# ble.net
KiCad netlist of a schematic drawn in Altium Designer
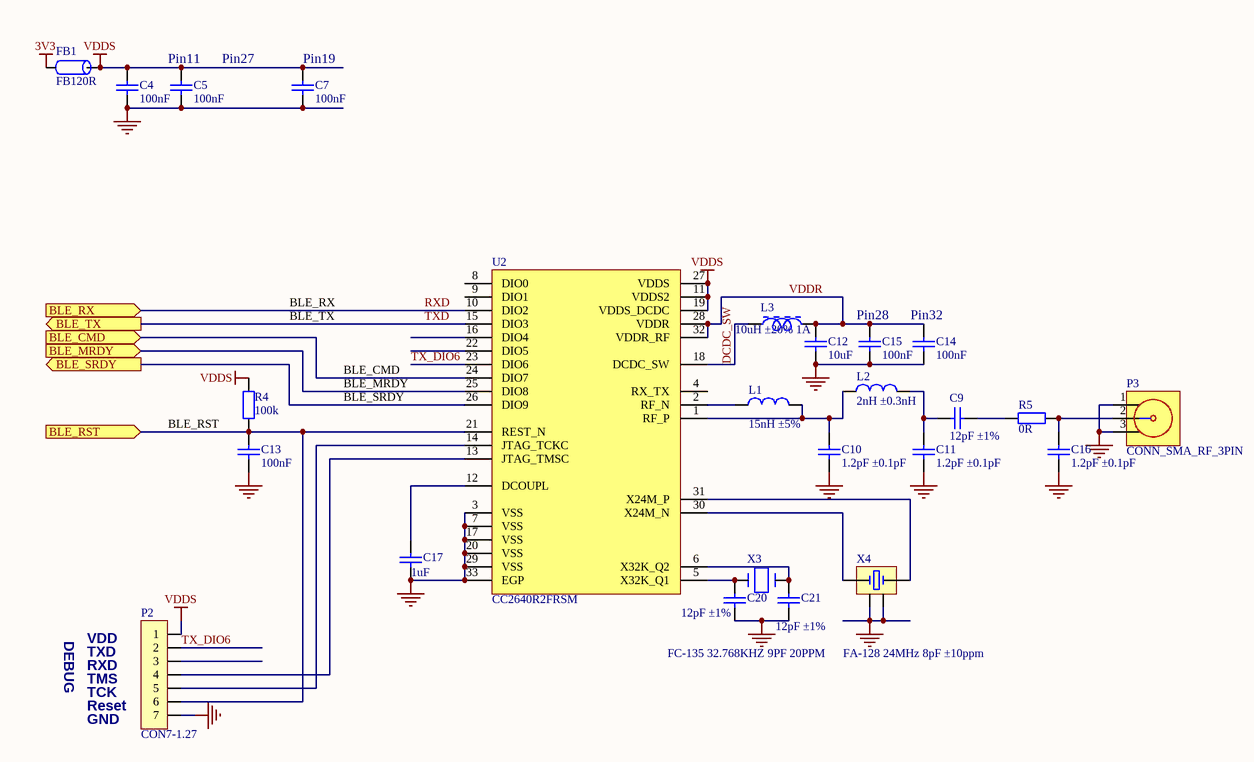
[diagram p0: ble.SchDoc]

(export (version "E")
  (design (tool "Eeschema 10.0.6"))
  (components
    (comp (ref "C4")
      (value "100nF")
      (footprint "0402_C")
      (description "表贴电容0402,±10%,16V,X7R")
      (fields (field (name "PART NUMBER") "RP02.04.000221") (field (name "PUBLISHER") "ChenYinaho"))
      (libsource (lib "tsl_Schlib") (part "Cap-0402_100n"))
    )
    (comp (ref "C5")
      (value "100nF")
      (footprint "0402_C")
      (description "表贴电容0402,±10%,16V,X7R")
      (fields (field (name "PART NUMBER") "RP02.04.000221") (field (name "PUBLISHER") "ChenYinaho"))
      (libsource (lib "tsl_Schlib") (part "Cap-0402_100n"))
    )
    (comp (ref "C7")
      (value "100nF")
      (footprint "0402_C")
      (description "表贴电容0402,±10%,16V,X7R")
      (fields (field (name "PART NUMBER") "RP02.04.000221") (field (name "PUBLISHER") "ChenYinaho"))
      (libsource (lib "tsl_Schlib") (part "Cap-0402_100n"))
    )
    (comp (ref "C9")
      (value "12pF ±1%")
      (footprint "0402_C")
      (description "表贴陶瓷电容,0402,±1%,50V,C0G")
      (fields
        (field (name "MANUFACTURER") "村田")
        (field (name "MANUFACTURER PART NUMBER") "GRM1555C1H120FA01D")
        (field (name "PUBLISHER") "ChenYinaho")
      )
      (libsource (lib "tsl_Schlib") (part "Cap-0402_12p_mu_1%"))
    )
    (comp (ref "C10")
      (value "1.2pF ±0.1pF")
      (footprint "0402_C")
      (description "表贴陶瓷电容,0402,±0.1pF,50V,C0G")
      (fields
        (field (name "MANUFACTURER") "村田")
        (field (name "MANUFACTURER PART NUMBER") "GRM1555C1H1R2BA01D")
        (field (name "PUBLISHER") "ChenYinaho")
      )
      (libsource (lib "tsl_Schlib") (part "Cap-0402_1.2p_mu"))
    )
    (comp (ref "C11")
      (value "1.2pF ±0.1pF")
      (footprint "0402_C")
      (description "表贴陶瓷电容,0402,±0.1pF,50V,C0G")
      (fields
        (field (name "MANUFACTURER") "村田")
        (field (name "MANUFACTURER PART NUMBER") "GRM1555C1H1R2BA01D")
        (field (name "PUBLISHER") "ChenYinaho")
      )
      (libsource (lib "tsl_Schlib") (part "Cap-0402_1.2p_mu"))
    )
    (comp (ref "C12")
      (value "10uF")
      (footprint "C0603")
      (description "表贴陶瓷电容,0603,±10%,10V")
      (fields
        (field (name "MANUFACTURER") "YAGO")
        (field (name "PART NUMBER") "RP02.04.000062")
        (field (name "PUBLISHER") "ChenYinaho")
      )
      (libsource (lib "tsl_Schlib") (part "Cap-SMT-0603_10u"))
    )
    (comp (ref "C13")
      (value "100nF")
      (footprint "0402_C")
      (description "表贴电容0402,±10%,16V,X7R")
      (fields (field (name "PART NUMBER") "RP02.04.000221") (field (name "PUBLISHER") "ChenYinaho"))
      (libsource (lib "tsl_Schlib") (part "Cap-0402_100n"))
    )
    (comp (ref "C14")
      (value "100nF")
      (footprint "0402_C")
      (description "表贴电容0402,±10%,16V,X7R")
      (fields (field (name "PART NUMBER") "RP02.04.000221") (field (name "PUBLISHER") "ChenYinaho"))
      (libsource (lib "tsl_Schlib") (part "Cap-0402_100n"))
    )
    (comp (ref "C15")
      (value "100nF")
      (footprint "0402_C")
      (description "表贴电容0402,±10%,16V,X7R")
      (fields (field (name "PART NUMBER") "RP02.04.000221") (field (name "PUBLISHER") "ChenYinaho"))
      (libsource (lib "tsl_Schlib") (part "Cap-0402_100n"))
    )
    (comp (ref "C16")
      (value "1.2pF ±0.1pF")
      (footprint "0402_C")
      (description "表贴陶瓷电容,0402,±0.1pF,50V,C0G")
      (fields
        (field (name "MANUFACTURER") "村田")
        (field (name "MANUFACTURER PART NUMBER") "GRM1555C1H1R2BA01D")
        (field (name "PUBLISHER") "ChenYinaho")
      )
      (libsource (lib "tsl_Schlib") (part "Cap-0402_1.2p_mu"))
    )
    (comp (ref "C17")
      (value "1uF")
      (footprint "0402_C")
      (description "表贴电容0402,±10%,6.3V")
      (fields (field (name "PART NUMBER") "RP02.04.000220") (field (name "PUBLISHER") "ChenYinaho"))
      (libsource (lib "tsl_Schlib") (part "Cap-0402_1u"))
    )
    (comp (ref "C20")
      (value "12pF ±1%")
      (footprint "0402_C")
      (description "表贴陶瓷电容,0402,±1%,50V,C0G")
      (fields
        (field (name "MANUFACTURER") "村田")
        (field (name "MANUFACTURER PART NUMBER") "GRM1555C1H120FA01D")
        (field (name "PUBLISHER") "ChenYinaho")
      )
      (libsource (lib "tsl_Schlib") (part "Cap-0402_12p_mu_1%"))
    )
    (comp (ref "C21")
      (value "12pF ±1%")
      (footprint "0402_C")
      (description "表贴陶瓷电容,0402,±1%,50V,C0G")
      (fields
        (field (name "MANUFACTURER") "村田")
        (field (name "MANUFACTURER PART NUMBER") "GRM1555C1H120FA01D")
        (field (name "PUBLISHER") "ChenYinaho")
      )
      (libsource (lib "tsl_Schlib") (part "Cap-0402_12p_mu_1%"))
    )
    (comp (ref "FB1")
      (value "FB120R")
      (footprint "L0603")
      (description "贴片磁珠")
      (fields
        (field (name "MANUFACTURER") "TDK")
        (field (name "PART NUMBER") "RP02.99.000093")
        (field (name "PUBLISHER") "ChenYinaho")
      )
      (libsource (lib "tsl_Schlib") (part "FB_0603_120R"))
    )
    (comp (ref "L1")
      (value "15nH ±5%")
      (footprint "LC-0402_L")
      (description "贴片电感 多层 0402 ±5% 450mA")
      (fields
        (field (name "MANUFACTURER") "村田")
        (field (name "MANUFACTURER PART NUMBER") "LQG15HS15NJ02D")
        (field (name "PUBLISHER") "ChenYinaho")
      )
      (libsource (lib "tsl_Schlib") (part "Inductor_0402_15nH"))
    )
    (comp (ref "L2")
      (value "2nH ±0.3nH")
      (footprint "LC-0402_L")
      (description "贴片电感 多层 0402 ±0.3nH 900mA")
      (fields
        (field (name "MANUFACTURER") "村田")
        (field (name "MANUFACTURER PART NUMBER") "LQG15HS2N0S02D")
        (field (name "PUBLISHER") "ChenYinaho")
      )
      (libsource (lib "tsl_Schlib") (part "Inductor_0402_2nH"))
    )
    (comp (ref "L3")
      (value "10uH ±20% 1A")
      (footprint "L0805")
      (description "贴片层叠电感")
      (fields
        (field (name "MANUFACTURER") "Sunlord")
        (field (name "MANUFACTURER PART NUMBER") "MPH201214S100MT")
        (field (name "PUBLISHER") "ChenYinaho")
      )
      (libsource (lib "tsl_Schlib") (part "Inductor_10uH_SL_0805"))
    )
    (comp (ref "P2")
      (value "CON7-1.27")
      (footprint "PH_7PIN_1.25_H-2")
      (description "直插插座")
      (fields (field (name "PART NUMBER") "RP02.07.000049") (field (name "PUBLISHER") "ChenYinaho"))
      (libsource (lib "tsl_Schlib") (part "CON7"))
    )
    (comp (ref "P3")
      (value "CONN_SMA_RF_3PIN")
      (footprint "PH_RF_2.5X2.5")
      (description "贴片天线座")
      (fields (field (name "PART NUMBER") "RP02.07.000078") (field (name "PUBLISHER") "ChenYinaho"))
      (libsource (lib "tsl_Schlib") (part "CONN_SMA_RF_3PIN"))
    )
    (comp (ref "R4")
      (value "100k")
      (footprint "0402_R")
      (description "表贴电阻,0402,±1%,1/16W")
      (fields (field (name "PART NUMBER") "NEW") (field (name "PUBLISHER") "ChenYinaho"))
      (libsource (lib "tsl_Schlib") (part "Res-0402_100k"))
    )
    (comp (ref "R5")
      (value "0R")
      (footprint "0402_R")
      (description "表贴电阻,0402,±1%,1/16W")
      (fields (field (name "PART NUMBER") "NEW") (field (name "PUBLISHER") "ChenYinaho"))
      (libsource (lib "tsl_Schlib") (part "Res-0402_0R"))
    )
    (comp (ref "U2")
      (value "CC2640R2FRSM")
      (footprint "VQFN-32_4x4x04P")
      (description "无线收发芯片")
      (fields
        (field (name "MANUFACTURER") "TI")
        (field (name "PART NUMBER") "NEW")
        (field (name "PUBLISHER") "ChenYinaho")
      )
      (libsource (lib "tsl_Schlib") (part "CC2640R2FRSM"))
    )
    (comp (ref "X3")
      (value "FC-135 32.768KHZ 9PF 20PPM")
      (footprint "FC-135")
      (description "贴片无源晶体3215")
      (fields
        (field (name "MANUFACTURER") "EPSON(爱普生)")
        (field (name "MANUFACTURER PART NUMBER") "FC-13532.768KHZ9PF20PPM")
        (field (name "PUBLISHER") "ChenYinaho")
      )
      (libsource (lib "tsl_Schlib") (part "XTAL-3215_2P_32k_9pF"))
    )
    (comp (ref "X4")
      (value "FA-128 24MHz 8pF ±10ppm")
      (footprint "FA-128")
      (description "贴片无源晶体2016")
      (fields
        (field (name "MANUFACTURER") "EPSON(爱普生)")
        (field (name "MANUFACTURER PART NUMBER") "Q22FA12800120")
        (field (name "PUBLISHER") "ChenYinaho")
      )
      (libsource (lib "tsl_Schlib") (part "XTAL-2016_4P_24M_8pF"))
    )
  )
  (nets
    (net (code "1") (name "/BLE_CMD") (class "Default")
      (node (ref "U2") (pin "24") (pinfunction "DIO7_24") (pintype "passive"))
    )
    (net (code "2") (name "/BLE_MRDY") (class "Default")
      (node (ref "U2") (pin "25") (pinfunction "DIO8_25") (pintype "passive"))
    )
    (net (code "3") (name "/BLE_RST") (class "Default")
      (node (ref "C13") (pin "1") (pinfunction "1_1") (pintype "passive"))
      (node (ref "P2") (pin "6") (pinfunction "6_6") (pintype "passive"))
      (node (ref "R4") (pin "1") (pinfunction "1_1") (pintype "passive"))
      (node (ref "U2") (pin "21") (pinfunction "REST_N_21") (pintype "passive"))
    )
    (net (code "4") (name "/BLE_RX") (class "Default")
      (node (ref "U2") (pin "10") (pinfunction "DIO2_10") (pintype "passive"))
    )
    (net (code "5") (name "/BLE_SRDY") (class "Default")
      (node (ref "U2") (pin "26") (pinfunction "DIO9_26") (pintype "passive"))
    )
    (net (code "6") (name "/BLE_TX") (class "Default")
      (node (ref "U2") (pin "15") (pinfunction "DIO3_15") (pintype "passive"))
    )
    (net (code "7") (name "/DCDC_SW") (class "Default")
      (node (ref "L3") (pin "2") (pintype "passive"))
      (node (ref "U2") (pin "18") (pinfunction "DCDC_SW_18") (pintype "passive"))
    )
    (net (code "8") (name "/TX_DIO6") (class "Default")
      (node (ref "P2") (pin "2") (pinfunction "2_2") (pintype "passive"))
      (node (ref "U2") (pin "23") (pinfunction "DIO6_23") (pintype "passive"))
    )
    (net (code "9") (name "/VDDR") (class "Default")
      (node (ref "C12") (pin "2") (pinfunction "2_2") (pintype "passive"))
      (node (ref "C14") (pin "1") (pinfunction "1_1") (pintype "passive"))
      (node (ref "C15") (pin "1") (pinfunction "1_1") (pintype "passive"))
      (node (ref "L3") (pin "1") (pintype "passive"))
      (node (ref "U2") (pin "28") (pinfunction "VDDR_28") (pintype "passive"))
      (node (ref "U2") (pin "32") (pinfunction "VDDR_RF_32") (pintype "passive"))
    )
    (net (code "10") (name "3V3") (class "Default") (node (ref "FB1") (pin "2") (pintype "passive")))
    (net (code "11") (name "GND") (class "Default")
      (node (ref "C10") (pin "1") (pinfunction "1_1") (pintype "passive"))
      (node (ref "C11") (pin "1") (pinfunction "1_1") (pintype "passive"))
      (node (ref "C12") (pin "1") (pinfunction "1_1") (pintype "passive"))
      (node (ref "C13") (pin "2") (pinfunction "2_2") (pintype "passive"))
      (node (ref "C14") (pin "2") (pinfunction "2_2") (pintype "passive"))
      (node (ref "C15") (pin "2") (pinfunction "2_2") (pintype "passive"))
      (node (ref "C16") (pin "1") (pinfunction "1_1") (pintype "passive"))
      (node (ref "C17") (pin "2") (pinfunction "2_2") (pintype "passive"))
      (node (ref "C20") (pin "1") (pinfunction "1_1") (pintype "passive"))
      (node (ref "C21") (pin "1") (pinfunction "1_1") (pintype "passive"))
      (node (ref "C4") (pin "2") (pinfunction "2_2") (pintype "passive"))
      (node (ref "C5") (pin "2") (pinfunction "2_2") (pintype "passive"))
      (node (ref "C7") (pin "2") (pinfunction "2_2") (pintype "passive"))
      (node (ref "P2") (pin "7") (pinfunction "7_7") (pintype "passive"))
      (node (ref "P3") (pin "1") (pintype "passive"))
      (node (ref "P3") (pin "3") (pintype "passive"))
      (node (ref "U2") (pin "17") (pinfunction "VSS_17") (pintype "passive"))
      (node (ref "U2") (pin "20") (pinfunction "VSS_20") (pintype "passive"))
      (node (ref "U2") (pin "29") (pinfunction "VSS_29") (pintype "passive"))
      (node (ref "U2") (pin "3") (pinfunction "VSS_3") (pintype "passive"))
      (node (ref "U2") (pin "33") (pinfunction "EGP_33") (pintype "passive"))
      (node (ref "U2") (pin "7") (pinfunction "VSS_7") (pintype "passive"))
      (node (ref "X4") (pin "2") (pintype "passive"))
      (node (ref "X4") (pin "4") (pintype "passive"))
    )
    (net (code "12") (name "Net-(C9-Pad1)") (class "Default")
      (node (ref "C9") (pin "1") (pinfunction "1_1") (pintype "passive"))
      (node (ref "R5") (pin "2") (pinfunction "2_2") (pintype "passive"))
    )
    (net (code "13") (name "Net-(C11-Pad2)") (class "Default")
      (node (ref "C11") (pin "2") (pinfunction "2_2") (pintype "passive"))
      (node (ref "C9") (pin "2") (pinfunction "2_2") (pintype "passive"))
      (node (ref "L2") (pin "1") (pintype "passive"))
    )
    (net (code "14") (name "Net-(C16-Pad2)") (class "Default")
      (node (ref "C16") (pin "2") (pinfunction "2_2") (pintype "passive"))
      (node (ref "P3") (pin "2") (pintype "passive"))
      (node (ref "R5") (pin "1") (pinfunction "1_1") (pintype "passive"))
    )
    (net (code "15") (name "Net-(U2-DCOUPL)") (class "Default")
      (node (ref "C17") (pin "1") (pinfunction "1_1") (pintype "passive"))
      (node (ref "U2") (pin "12") (pinfunction "DCOUPL_12") (pintype "passive"))
    )
    (net (code "16") (name "Net-(U2-JTAG_TCKC)") (class "Default")
      (node (ref "P2") (pin "5") (pinfunction "5_5") (pintype "passive"))
      (node (ref "U2") (pin "14") (pinfunction "JTAG_TCKC_14") (pintype "passive"))
    )
    (net (code "17") (name "Net-(U2-JTAG_TMSC)") (class "Default")
      (node (ref "P2") (pin "4") (pinfunction "4_4") (pintype "passive"))
      (node (ref "U2") (pin "13") (pinfunction "JTAG_TMSC_13") (pintype "passive"))
    )
    (net (code "18") (name "Net-(U2-RF_N)") (class "Default")
      (node (ref "L1") (pin "2") (pintype "passive"))
      (node (ref "U2") (pin "2") (pinfunction "RF_N_2") (pintype "passive"))
    )
    (net (code "19") (name "Net-(U2-RF_P)") (class "Default")
      (node (ref "C10") (pin "2") (pinfunction "2_2") (pintype "passive"))
      (node (ref "L1") (pin "1") (pintype "passive"))
      (node (ref "L2") (pin "2") (pintype "passive"))
      (node (ref "U2") (pin "1") (pinfunction "RF_P_1") (pintype "passive"))
    )
    (net (code "20") (name "Net-(U2-X24M_N)") (class "Default")
      (node (ref "U2") (pin "30") (pinfunction "X24M_N_30") (pintype "passive"))
      (node (ref "X4") (pin "1") (pintype "passive"))
    )
    (net (code "21") (name "Net-(U2-X24M_P)") (class "Default")
      (node (ref "U2") (pin "31") (pinfunction "X24M_P_31") (pintype "passive"))
      (node (ref "X4") (pin "3") (pintype "passive"))
    )
    (net (code "22") (name "Net-(U2-X32K_Q1)") (class "Default")
      (node (ref "C20") (pin "2") (pinfunction "2_2") (pintype "passive"))
      (node (ref "U2") (pin "5") (pinfunction "X32K_Q1_5") (pintype "passive"))
      (node (ref "X3") (pin "2") (pintype "passive"))
    )
    (net (code "23") (name "Net-(U2-X32K_Q2)") (class "Default")
      (node (ref "C21") (pin "2") (pinfunction "2_2") (pintype "passive"))
      (node (ref "U2") (pin "6") (pinfunction "X32K_Q2_6") (pintype "passive"))
      (node (ref "X3") (pin "1") (pintype "passive"))
    )
    (net (code "24") (name "VDDS") (class "Default")
      (node (ref "C4") (pin "1") (pinfunction "1_1") (pintype "passive"))
      (node (ref "C5") (pin "1") (pinfunction "1_1") (pintype "passive"))
      (node (ref "C7") (pin "1") (pinfunction "1_1") (pintype "passive"))
      (node (ref "FB1") (pin "1") (pintype "passive"))
      (node (ref "P2") (pin "1") (pinfunction "1_1") (pintype "passive"))
      (node (ref "R4") (pin "2") (pinfunction "2_2") (pintype "passive"))
      (node (ref "U2") (pin "11") (pinfunction "VDDS2_11") (pintype "passive"))
      (node (ref "U2") (pin "19") (pinfunction "VDDS_DCDC_19") (pintype "passive"))
      (node (ref "U2") (pin "27") (pinfunction "VDDS_27") (pintype "passive"))
    )
    (net (code "25") (name "unconnected-(P2-Pad3)") (class "Default")
      (node (ref "P2") (pin "3") (pinfunction "3_3") (pintype "passive"))
    )
    (net (code "26") (name "unconnected-(U2-DIO0-Pad8)") (class "Default")
      (node (ref "U2") (pin "8") (pinfunction "DIO0_8") (pintype "passive"))
    )
    (net (code "27") (name "unconnected-(U2-DIO1-Pad9)") (class "Default")
      (node (ref "U2") (pin "9") (pinfunction "DIO1_9") (pintype "passive"))
    )
    (net (code "28") (name "unconnected-(U2-DIO4-Pad16)") (class "Default")
      (node (ref "U2") (pin "16") (pinfunction "DIO4_16") (pintype "passive"))
    )
    (net (code "29") (name "unconnected-(U2-DIO5-Pad22)") (class "Default")
      (node (ref "U2") (pin "22") (pinfunction "DIO5_22") (pintype "passive"))
    )
    (net (code "30") (name "unconnected-(U2-RX_TX-Pad4)") (class "Default")
      (node (ref "U2") (pin "4") (pinfunction "RX_TX_4") (pintype "passive"))
    )
  )
)
